# lab3.net
KiCad netlist of a schematic drawn in EAGLE
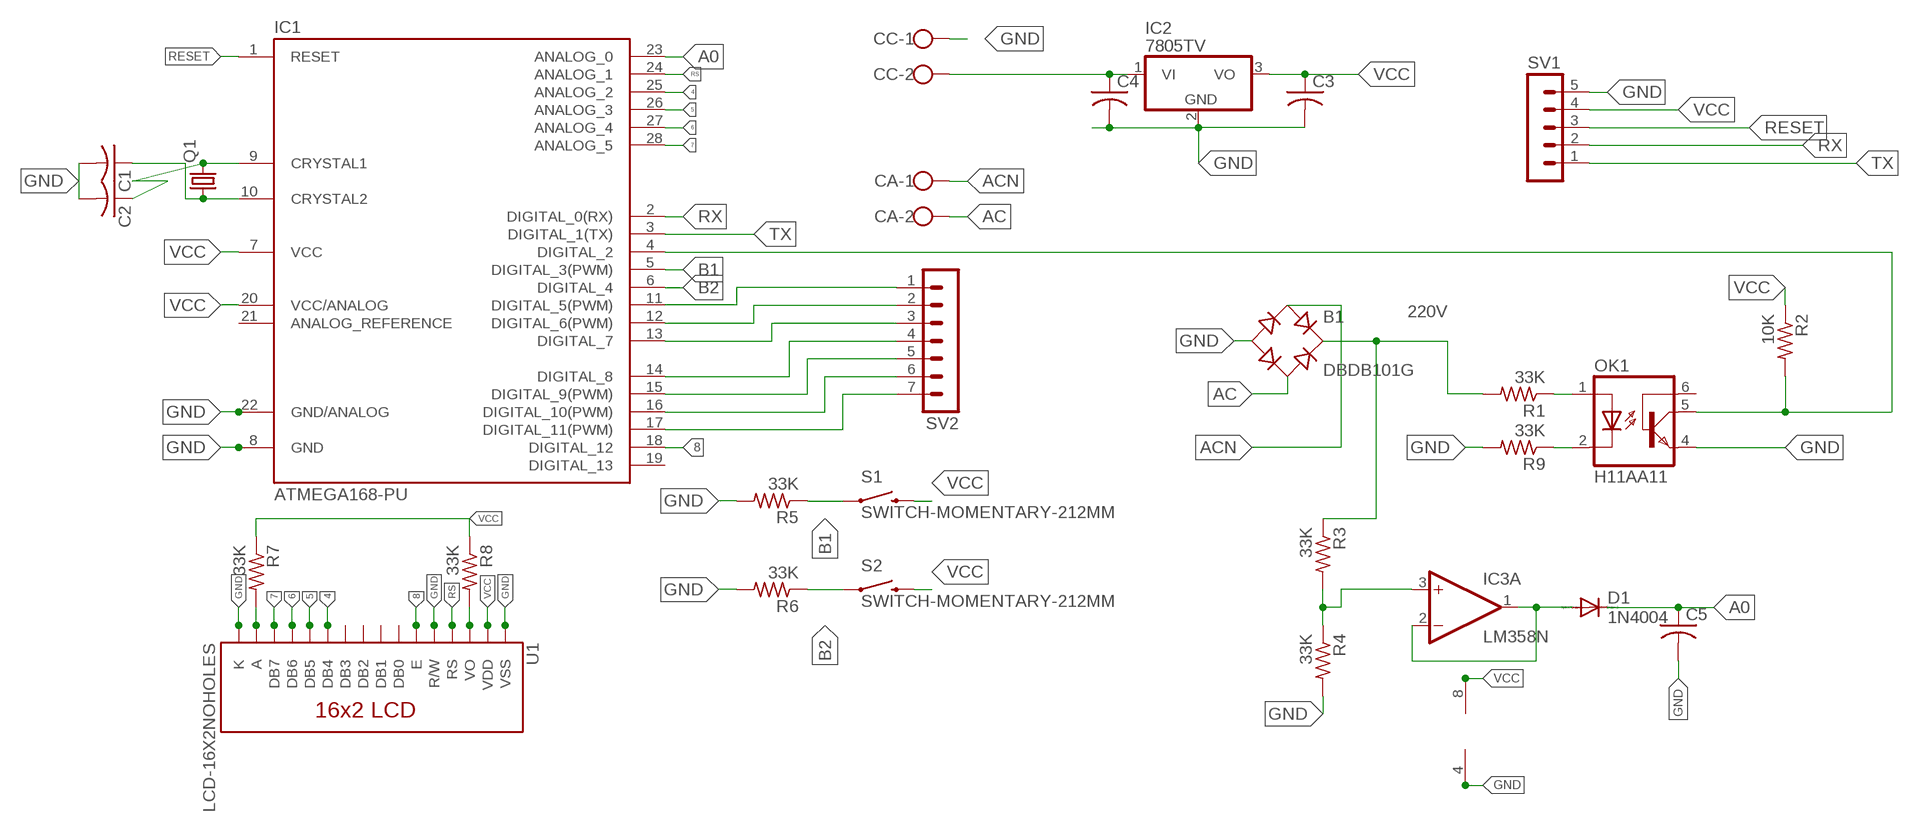
[diagram p0: schematic, sheet 1]

(export (version "E")
  (design (tool "Eeschema 10.0.6"))
  (components
    (comp (ref "B1")
      (value "DBDB101G")
      (footprint "eagle-import:DB")
      (libsource (lib "eagle-import") (part "DB?GDB101"))
    )
    (comp (ref "C1")
      (value "C-US025-025X050")
      (footprint "eagle-import:C025-025X050")
      (libsource (lib "eagle-import") (part "C-US025-025X050"))
    )
    (comp (ref "C2")
      (value "C-US025-025X050")
      (footprint "eagle-import:C025-025X050")
      (libsource (lib "eagle-import") (part "C-US025-025X050"))
    )
    (comp (ref "C3")
      (value "C-US050-025X075")
      (footprint "eagle-import:C050-025X075")
      (libsource (lib "eagle-import") (part "C-US050-025X075"))
    )
    (comp (ref "C4")
      (value "C-US050-025X075")
      (footprint "eagle-import:C050-025X075")
      (libsource (lib "eagle-import") (part "C-US050-025X075"))
    )
    (comp (ref "C5")
      (value "C-US050-025X075")
      (footprint "eagle-import:C050-025X075")
      (libsource (lib "eagle-import") (part "C-US050-025X075"))
    )
    (comp (ref "CA")
      (value "W237-102")
      (footprint "eagle-import:W237-102")
      (fields (field (name "MPN") "237-102"))
      (libsource (lib "eagle-import") (part "W237-102"))
    )
    (comp (ref "CC")
      (value "W237-102")
      (footprint "eagle-import:W237-102")
      (fields (field (name "MPN") "237-102"))
      (libsource (lib "eagle-import") (part "W237-102"))
    )
    (comp (ref "D1")
      (value "1N4004")
      (footprint "eagle-import:DO41-10")
      (libsource (lib "eagle-import") (part "1N4004"))
    )
    (comp (ref "IC1")
      (value "ATMEGA168-PU")
      (footprint "eagle-import:DIL28-3")
      (libsource (lib "eagle-import") (part "ATMEGA168-PU"))
    )
    (comp (ref "IC2")
      (value "7805TV")
      (footprint "eagle-import:TO220V")
      (libsource (lib "eagle-import") (part "78TV05"))
    )
    (comp (ref "IC3")
      (value "LM358N")
      (footprint "eagle-import:DIL08")
      (libsource (lib "eagle-import") (part "LM358N"))
    )
    (comp (ref "OK1")
      (value "H11AA11")
      (footprint "eagle-import:DIL06")
      (fields (field (name "MPN") "H11A1-M"))
      (libsource (lib "eagle-import") (part "H11AA11"))
    )
    (comp (ref "Q1")
      (value "CRYSTALHC18U-V")
      (footprint "eagle-import:HC18U-V")
      (libsource (lib "eagle-import") (part "CRYSTALHC18U-V"))
    )
    (comp (ref "R1")
      (value "33K")
      (footprint "eagle-import:0207_7")
      (libsource (lib "eagle-import") (part "R-US_0207/7"))
    )
    (comp (ref "R2")
      (value "10K")
      (footprint "eagle-import:0207_7")
      (libsource (lib "eagle-import") (part "R-US_0207/7"))
    )
    (comp (ref "R3")
      (value "33K")
      (footprint "eagle-import:0207_7")
      (libsource (lib "eagle-import") (part "R-US_0207/7"))
    )
    (comp (ref "R4")
      (value "33K")
      (footprint "eagle-import:0207_7")
      (libsource (lib "eagle-import") (part "R-US_0207/7"))
    )
    (comp (ref "R5")
      (value "33K")
      (footprint "eagle-import:0207_7")
      (libsource (lib "eagle-import") (part "R-US_0207/7"))
    )
    (comp (ref "R6")
      (value "33K")
      (footprint "eagle-import:0207_7")
      (libsource (lib "eagle-import") (part "R-US_0207/7"))
    )
    (comp (ref "R7")
      (value "33K")
      (footprint "eagle-import:0207_7")
      (libsource (lib "eagle-import") (part "R-US_0207/7"))
    )
    (comp (ref "R8")
      (value "33K")
      (footprint "eagle-import:0207_7")
      (libsource (lib "eagle-import") (part "R-US_0207/7"))
    )
    (comp (ref "R9")
      (value "33K")
      (footprint "eagle-import:0207_7")
      (libsource (lib "eagle-import") (part "R-US_0207/7"))
    )
    (comp (ref "S1")
      (value "SWITCH-MOMENTARY-212MM")
      (footprint "eagle-import:TACTILE-PTH-12MM")
      (libsource (lib "eagle-import") (part "SWITCH-MOMENTARY-212MM"))
    )
    (comp (ref "S2")
      (value "SWITCH-MOMENTARY-212MM")
      (footprint "eagle-import:TACTILE-PTH-12MM")
      (libsource (lib "eagle-import") (part "SWITCH-MOMENTARY-212MM"))
    )
    (comp (ref "SV1")
      (value "MA05-1")
      (footprint "eagle-import:MA05-1")
      (libsource (lib "eagle-import") (part "MA05-1"))
    )
    (comp (ref "SV2")
      (value "MA07-1")
      (footprint "eagle-import:MA07-1")
      (libsource (lib "eagle-import") (part "MA07-1"))
    )
    (comp (ref "U1")
      (value "LCD-16X2NOHOLES")
      (footprint "eagle-import:LCD-16X2_NOHOLES")
      (libsource (lib "eagle-import") (part "LCD-16X2NOHOLES"))
    )
  )
  (nets
    (net (code "1") (name "/220V") (class "Default")
      (node (ref "B1") (pin "+") (pinfunction "+_+") (pintype "passive"))
      (node (ref "R1") (pin "2") (pinfunction "2_2") (pintype "passive"))
      (node (ref "R3") (pin "1") (pinfunction "1_1") (pintype "passive"))
    )
    (net (code "2") (name "4") (class "Default")
      (node (ref "IC1") (pin "25") (pinfunction "ANALOG_2_25") (pintype "bidirectional"))
      (node (ref "U1") (pin "11") (pinfunction "DB4_11") (pintype "bidirectional"))
    )
    (net (code "3") (name "5") (class "Default")
      (node (ref "IC1") (pin "26") (pinfunction "ANALOG_3_26") (pintype "bidirectional"))
      (node (ref "U1") (pin "12") (pinfunction "DB5_12") (pintype "bidirectional"))
    )
    (net (code "4") (name "6") (class "Default")
      (node (ref "IC1") (pin "27") (pinfunction "ANALOG_4_27") (pintype "bidirectional"))
      (node (ref "U1") (pin "13") (pinfunction "DB6_13") (pintype "bidirectional"))
    )
    (net (code "5") (name "7") (class "Default")
      (node (ref "IC1") (pin "28") (pinfunction "ANALOG_5_28") (pintype "bidirectional"))
      (node (ref "U1") (pin "14") (pinfunction "DB7_14") (pintype "bidirectional"))
    )
    (net (code "6") (name "8") (class "Default")
      (node (ref "IC1") (pin "18") (pinfunction "DIGITAL_12_18") (pintype "bidirectional"))
      (node (ref "U1") (pin "6") (pinfunction "E_6") (pintype "input"))
    )
    (net (code "7") (name "A0") (class "Default")
      (node (ref "C5") (pin "1") (pinfunction "1_1") (pintype "passive"))
      (node (ref "D1") (pin "C") (pinfunction "C_C") (pintype "passive"))
      (node (ref "IC1") (pin "23") (pinfunction "ANALOG_0_23") (pintype "bidirectional"))
    )
    (net (code "8") (name "AC") (class "Default")
      (node (ref "B1") (pin "AC2") (pinfunction "AC2_AC2") (pintype "passive"))
      (node (ref "CA") (pin "2") (pinfunction "KL_2") (pintype "passive"))
    )
    (net (code "9") (name "ACN") (class "Default")
      (node (ref "B1") (pin "AC1") (pinfunction "AC1_AC1") (pintype "passive"))
      (node (ref "CA") (pin "1") (pinfunction "KL_1") (pintype "passive"))
    )
    (net (code "10") (name "B1") (class "Default")
      (node (ref "IC1") (pin "5") (pinfunction "DIGITAL_3(PWM)_5") (pintype "bidirectional"))
      (node (ref "R5") (pin "1") (pinfunction "1_1") (pintype "passive"))
      (node (ref "S1") (pin "1") (pinfunction "1_1") (pintype "passive"))
    )
    (net (code "11") (name "B2") (class "Default")
      (node (ref "IC1") (pin "6") (pinfunction "DIGITAL_4_6") (pintype "bidirectional"))
      (node (ref "R6") (pin "1") (pinfunction "1_1") (pintype "passive"))
      (node (ref "S2") (pin "1") (pinfunction "1_1") (pintype "passive"))
    )
    (net (code "12") (name "GND") (class "Default")
      (node (ref "B1") (pin "-") (pinfunction "-_-") (pintype "passive"))
      (node (ref "C1") (pin "2") (pinfunction "2_2") (pintype "passive"))
      (node (ref "C2") (pin "2") (pinfunction "2_2") (pintype "passive"))
      (node (ref "C3") (pin "2") (pinfunction "2_2") (pintype "passive"))
      (node (ref "C4") (pin "2") (pinfunction "2_2") (pintype "passive"))
      (node (ref "C5") (pin "2") (pinfunction "2_2") (pintype "passive"))
      (node (ref "CC") (pin "1") (pinfunction "KL_1") (pintype "passive"))
      (node (ref "IC1") (pin "22") (pinfunction "GND/ANALOG_22") (pintype "power_in"))
      (node (ref "IC1") (pin "8") (pinfunction "GND_8") (pintype "power_in"))
      (node (ref "IC2") (pin "2") (pinfunction "GND_2") (pintype "passive"))
      (node (ref "IC3") (pin "4") (pinfunction "V-_4") (pintype "power_in"))
      (node (ref "OK1") (pin "4") (pinfunction "EMI_4") (pintype "passive"))
      (node (ref "R4") (pin "2") (pinfunction "2_2") (pintype "passive"))
      (node (ref "R5") (pin "2") (pinfunction "2_2") (pintype "passive"))
      (node (ref "R6") (pin "2") (pinfunction "2_2") (pintype "passive"))
      (node (ref "R9") (pin "2") (pinfunction "2_2") (pintype "passive"))
      (node (ref "SV1") (pin "5") (pinfunction "5_5") (pintype "passive"))
      (node (ref "U1") (pin "1") (pinfunction "VSS_1") (pintype "power_in"))
      (node (ref "U1") (pin "16") (pinfunction "K_16") (pintype "power_in"))
      (node (ref "U1") (pin "5") (pinfunction "R/W_5") (pintype "input"))
    )
    (net (code "13") (name "Net-(CCB-KL)") (class "Default")
      (node (ref "C4") (pin "1") (pinfunction "1_1") (pintype "passive"))
      (node (ref "CC") (pin "2") (pinfunction "KL_2") (pintype "passive"))
      (node (ref "IC2") (pin "1") (pinfunction "VI_1") (pintype "input"))
    )
    (net (code "14") (name "Net-(IC1-CRYSTAL1)") (class "Default")
      (node (ref "C2") (pin "1") (pinfunction "1_1") (pintype "passive"))
      (node (ref "IC1") (pin "9") (pinfunction "CRYSTAL1_9") (pintype "bidirectional"))
      (node (ref "Q1") (pin "2") (pinfunction "2_2") (pintype "passive"))
    )
    (net (code "15") (name "Net-(IC1-CRYSTAL2)") (class "Default")
      (node (ref "C1") (pin "1") (pinfunction "1_1") (pintype "passive"))
      (node (ref "IC1") (pin "10") (pinfunction "CRYSTAL2_10") (pintype "bidirectional"))
      (node (ref "Q1") (pin "1") (pinfunction "1_1") (pintype "passive"))
    )
    (net (code "16") (name "Net-(IC1-DIGITAL_2)") (class "Default")
      (node (ref "IC1") (pin "4") (pinfunction "DIGITAL_2_4") (pintype "bidirectional"))
      (node (ref "OK1") (pin "5") (pinfunction "COL_5") (pintype "passive"))
      (node (ref "R2") (pin "2") (pinfunction "2_2") (pintype "passive"))
    )
    (net (code "17") (name "Net-(IC1-DIGITAL_5(PWM))") (class "Default")
      (node (ref "IC1") (pin "11") (pinfunction "DIGITAL_5(PWM)_11") (pintype "bidirectional"))
      (node (ref "SV2") (pin "1") (pinfunction "1_1") (pintype "passive"))
    )
    (net (code "18") (name "Net-(IC1-DIGITAL_6(PWM))") (class "Default")
      (node (ref "IC1") (pin "12") (pinfunction "DIGITAL_6(PWM)_12") (pintype "bidirectional"))
      (node (ref "SV2") (pin "2") (pinfunction "2_2") (pintype "passive"))
    )
    (net (code "19") (name "Net-(IC1-DIGITAL_7)") (class "Default")
      (node (ref "IC1") (pin "13") (pinfunction "DIGITAL_7_13") (pintype "bidirectional"))
      (node (ref "SV2") (pin "3") (pinfunction "3_3") (pintype "passive"))
    )
    (net (code "20") (name "Net-(IC1-DIGITAL_8)") (class "Default")
      (node (ref "IC1") (pin "14") (pinfunction "DIGITAL_8_14") (pintype "bidirectional"))
      (node (ref "SV2") (pin "4") (pinfunction "4_4") (pintype "passive"))
    )
    (net (code "21") (name "Net-(IC1-DIGITAL_9(PWM))") (class "Default")
      (node (ref "IC1") (pin "15") (pinfunction "DIGITAL_9(PWM)_15") (pintype "bidirectional"))
      (node (ref "SV2") (pin "5") (pinfunction "5_5") (pintype "passive"))
    )
    (net (code "22") (name "Net-(IC1-DIGITAL_10(PWM))") (class "Default")
      (node (ref "IC1") (pin "16") (pinfunction "DIGITAL_10(PWM)_16") (pintype "bidirectional"))
      (node (ref "SV2") (pin "6") (pinfunction "6_6") (pintype "passive"))
    )
    (net (code "23") (name "Net-(IC1-DIGITAL_11(PWM))") (class "Default")
      (node (ref "IC1") (pin "17") (pinfunction "DIGITAL_11(PWM)_17") (pintype "bidirectional"))
      (node (ref "SV2") (pin "7") (pinfunction "7_7") (pintype "passive"))
    )
    (net (code "24") (name "Net-(IC3A-+IN)") (class "Default")
      (node (ref "IC3") (pin "3") (pinfunction "+IN_3") (pintype "input"))
      (node (ref "R3") (pin "2") (pinfunction "2_2") (pintype "passive"))
      (node (ref "R4") (pin "1") (pinfunction "1_1") (pintype "passive"))
    )
    (net (code "25") (name "Net-(IC3A--IN)") (class "Default")
      (node (ref "D1") (pin "A") (pinfunction "A_A") (pintype "passive"))
      (node (ref "IC3") (pin "1") (pinfunction "OUT_1") (pintype "output"))
      (node (ref "IC3") (pin "2") (pinfunction "-IN_2") (pintype "input"))
    )
    (net (code "26") (name "Net-(OK1-A)") (class "Default")
      (node (ref "OK1") (pin "1") (pinfunction "A_1") (pintype "passive"))
      (node (ref "R1") (pin "1") (pinfunction "1_1") (pintype "passive"))
    )
    (net (code "27") (name "Net-(OK1-C)") (class "Default")
      (node (ref "OK1") (pin "2") (pinfunction "C_2") (pintype "passive"))
      (node (ref "R9") (pin "1") (pinfunction "1_1") (pintype "passive"))
    )
    (net (code "28") (name "Net-(U1-A)") (class "Default")
      (node (ref "R7") (pin "2") (pinfunction "2_2") (pintype "passive"))
      (node (ref "U1") (pin "15") (pinfunction "A_15") (pintype "power_in"))
    )
    (net (code "29") (name "Net-(U1-VO)") (class "Default")
      (node (ref "R8") (pin "2") (pinfunction "2_2") (pintype "passive"))
      (node (ref "U1") (pin "3") (pinfunction "VO_3") (pintype "bidirectional"))
    )
    (net (code "30") (name "RESET") (class "Default")
      (node (ref "IC1") (pin "1") (pinfunction "RESET_1") (pintype "bidirectional"))
      (node (ref "SV1") (pin "3") (pinfunction "3_3") (pintype "passive"))
    )
    (net (code "31") (name "RS") (class "Default")
      (node (ref "IC1") (pin "24") (pinfunction "ANALOG_1_24") (pintype "bidirectional"))
      (node (ref "U1") (pin "4") (pinfunction "RS_4") (pintype "input"))
    )
    (net (code "32") (name "RX") (class "Default")
      (node (ref "IC1") (pin "2") (pinfunction "DIGITAL_0(RX)_2") (pintype "bidirectional"))
      (node (ref "SV1") (pin "2") (pinfunction "2_2") (pintype "passive"))
    )
    (net (code "33") (name "TX") (class "Default")
      (node (ref "IC1") (pin "3") (pinfunction "DIGITAL_1(TX)_3") (pintype "bidirectional"))
      (node (ref "SV1") (pin "1") (pinfunction "1_1") (pintype "passive"))
    )
    (net (code "34") (name "VCC") (class "Default")
      (node (ref "C3") (pin "1") (pinfunction "1_1") (pintype "passive"))
      (node (ref "IC1") (pin "20") (pinfunction "VCC/ANALOG_20") (pintype "passive"))
      (node (ref "IC1") (pin "7") (pinfunction "VCC_7") (pintype "power_in"))
      (node (ref "IC2") (pin "3") (pinfunction "VO_3") (pintype "passive"))
      (node (ref "IC3") (pin "8") (pinfunction "V+_8") (pintype "power_in"))
      (node (ref "R2") (pin "1") (pinfunction "1_1") (pintype "passive"))
      (node (ref "R7") (pin "1") (pinfunction "1_1") (pintype "passive"))
      (node (ref "R8") (pin "1") (pinfunction "1_1") (pintype "passive"))
      (node (ref "S1") (pin "3") (pinfunction "2_3") (pintype "passive"))
      (node (ref "S2") (pin "3") (pinfunction "2_3") (pintype "passive"))
      (node (ref "SV1") (pin "4") (pinfunction "4_4") (pintype "passive"))
      (node (ref "U1") (pin "2") (pinfunction "VDD_2") (pintype "power_in"))
    )
    (net (code "35") (name "unconnected-(IC1-ANALOG_REFERENCE-Pad21)") (class "Default")
      (node (ref "IC1") (pin "21") (pinfunction "ANALOG_REFERENCE_21") (pintype "passive"))
    )
    (net (code "36") (name "unconnected-(IC1-DIGITAL_13-Pad19)") (class "Default")
      (node (ref "IC1") (pin "19") (pinfunction "DIGITAL_13_19") (pintype "bidirectional"))
    )
    (net (code "37") (name "unconnected-(OK1-BAS-Pad6)") (class "Default")
      (node (ref "OK1") (pin "6") (pinfunction "BAS_6") (pintype "passive"))
    )
    (net (code "38") (name "unconnected-(U1-DB0-Pad7)") (class "Default")
      (node (ref "U1") (pin "7") (pinfunction "DB0_7") (pintype "bidirectional"))
    )
    (net (code "39") (name "unconnected-(U1-DB1-Pad8)") (class "Default")
      (node (ref "U1") (pin "8") (pinfunction "DB1_8") (pintype "bidirectional"))
    )
    (net (code "40") (name "unconnected-(U1-DB2-Pad9)") (class "Default")
      (node (ref "U1") (pin "9") (pinfunction "DB2_9") (pintype "bidirectional"))
    )
    (net (code "41") (name "unconnected-(U1-DB3-Pad10)") (class "Default")
      (node (ref "U1") (pin "10") (pinfunction "DB3_10") (pintype "bidirectional"))
    )
  )
)
